# ledboard.net
KiCad netlist of a schematic drawn in EAGLE
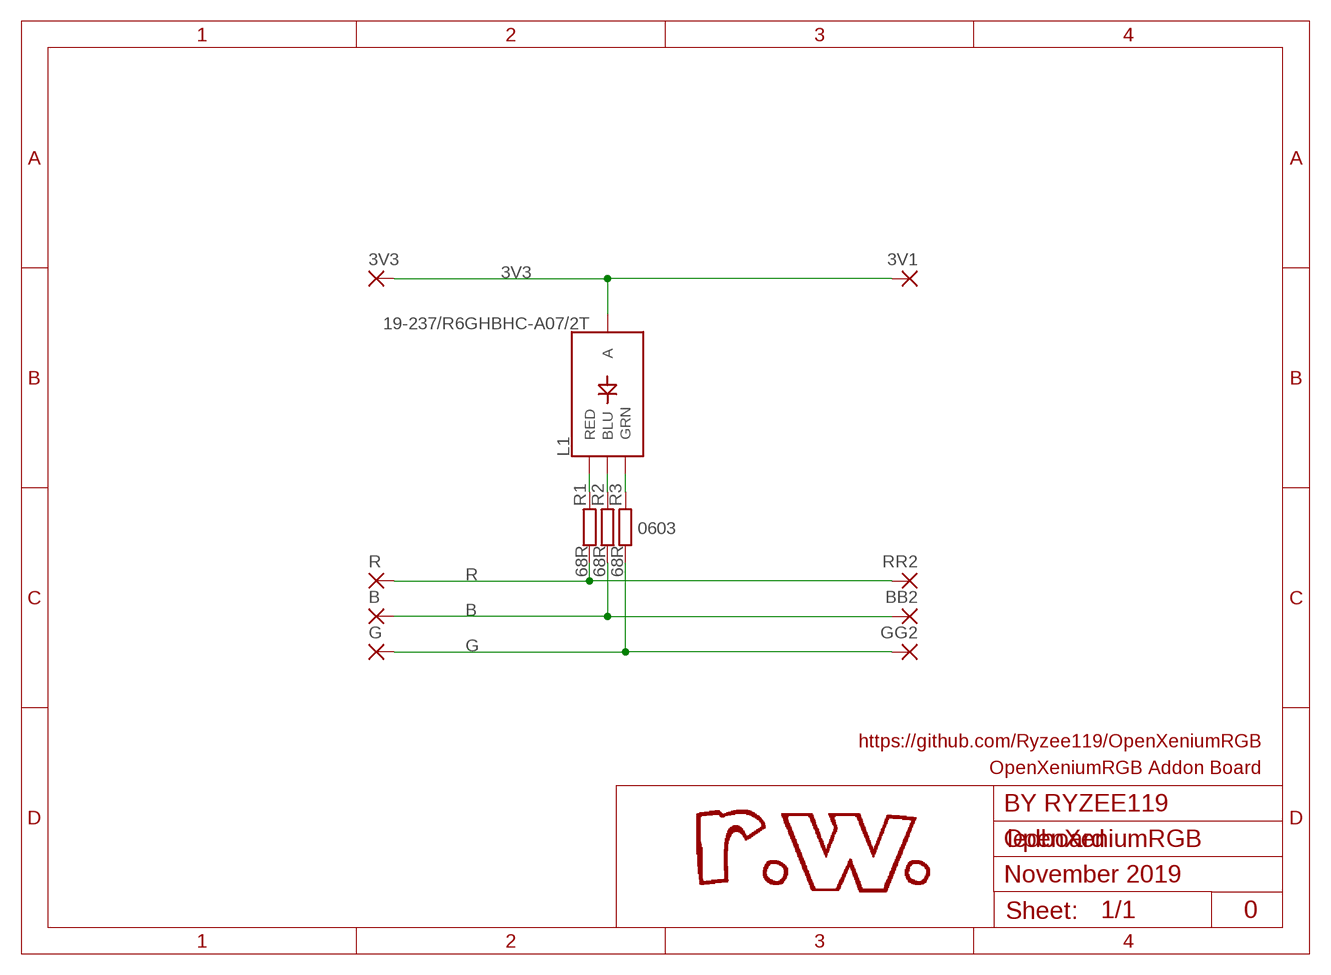
[diagram p0: schematic, sheet 1]

(export (version "E")
  (design (tool "Eeschema 10.0.6"))
  (components
    (comp (ref "3V1")
      (value "SMD2")
      (footprint "eagle-import:SMD1,27-2,54")
      (libsource (lib "eagle-import") (part "SMD2"))
    )
    (comp (ref "3V3")
      (value "SMD2")
      (footprint "eagle-import:SMD1,27-2,54")
      (libsource (lib "eagle-import") (part "SMD2"))
    )
    (comp (ref "B")
      (value "SMD2")
      (footprint "eagle-import:SMD1,27-2,54")
      (libsource (lib "eagle-import") (part "SMD2"))
    )
    (comp (ref "BB2")
      (value "SMD2")
      (footprint "eagle-import:SMD1,27-2,54")
      (libsource (lib "eagle-import") (part "SMD2"))
    )
    (comp (ref "G")
      (value "SMD2")
      (footprint "eagle-import:SMD1,27-2,54")
      (libsource (lib "eagle-import") (part "SMD2"))
    )
    (comp (ref "GG2")
      (value "SMD2")
      (footprint "eagle-import:SMD1,27-2,54")
      (libsource (lib "eagle-import") (part "SMD2"))
    )
    (comp (ref "L1")
      (value "19-237/R6GHBHC-A07/2T")
      (footprint "eagle-import:4-SMD-R6GHBHC")
      (libsource (lib "eagle-import") (part "19-237/R6GHBHC-A07/2T"))
    )
    (comp (ref "R")
      (value "SMD2")
      (footprint "eagle-import:SMD1,27-2,54")
      (libsource (lib "eagle-import") (part "SMD2"))
    )
    (comp (ref "R1")
      (value "68R")
      (footprint "eagle-import:R0603")
      (libsource (lib "eagle-import") (part "R-EU_R0603"))
    )
    (comp (ref "R2")
      (value "68R")
      (footprint "eagle-import:R0603")
      (libsource (lib "eagle-import") (part "R-EU_R0603"))
    )
    (comp (ref "R3")
      (value "68R")
      (footprint "eagle-import:R0603")
      (libsource (lib "eagle-import") (part "R-EU_R0603"))
    )
    (comp (ref "RR2")
      (value "SMD2")
      (footprint "eagle-import:SMD1,27-2,54")
      (libsource (lib "eagle-import") (part "SMD2"))
    )
  )
  (nets
    (net (code "1") (name "/3V3") (class "Default")
      (node (ref "3V1") (pin "1") (pinfunction "P_1") (pintype "passive"))
      (node (ref "3V3") (pin "1") (pinfunction "P_1") (pintype "passive"))
      (node (ref "L1") (pin "P$2") (pinfunction "A_P$2") (pintype "bidirectional"))
    )
    (net (code "2") (name "/B") (class "Default")
      (node (ref "B") (pin "1") (pinfunction "P_1") (pintype "passive"))
      (node (ref "BB2") (pin "1") (pinfunction "P_1") (pintype "passive"))
      (node (ref "R2") (pin "1") (pinfunction "1_1") (pintype "passive"))
    )
    (net (code "3") (name "/G") (class "Default")
      (node (ref "G") (pin "1") (pinfunction "P_1") (pintype "passive"))
      (node (ref "GG2") (pin "1") (pinfunction "P_1") (pintype "passive"))
      (node (ref "R3") (pin "1") (pinfunction "1_1") (pintype "passive"))
    )
    (net (code "4") (name "/R") (class "Default")
      (node (ref "R") (pin "1") (pinfunction "P_1") (pintype "passive"))
      (node (ref "R1") (pin "1") (pinfunction "1_1") (pintype "passive"))
      (node (ref "RR2") (pin "1") (pinfunction "P_1") (pintype "passive"))
    )
    (net (code "5") (name "Net-(L1-BLU)") (class "Default")
      (node (ref "L1") (pin "P$4") (pinfunction "BLU_P$4") (pintype "bidirectional"))
      (node (ref "R2") (pin "2") (pinfunction "2_2") (pintype "passive"))
    )
    (net (code "6") (name "Net-(L1-GRN)") (class "Default")
      (node (ref "L1") (pin "P$3") (pinfunction "GRN_P$3") (pintype "bidirectional"))
      (node (ref "R3") (pin "2") (pinfunction "2_2") (pintype "passive"))
    )
    (net (code "7") (name "Net-(L1-RED)") (class "Default")
      (node (ref "L1") (pin "P$1") (pinfunction "RED_P$1") (pintype "bidirectional"))
      (node (ref "R1") (pin "2") (pinfunction "2_2") (pintype "passive"))
    )
  )
)
